# OpenMV-Shield-DESKTOP-QOJ183D.net
KiCad netlist of a schematic drawn in EAGLE
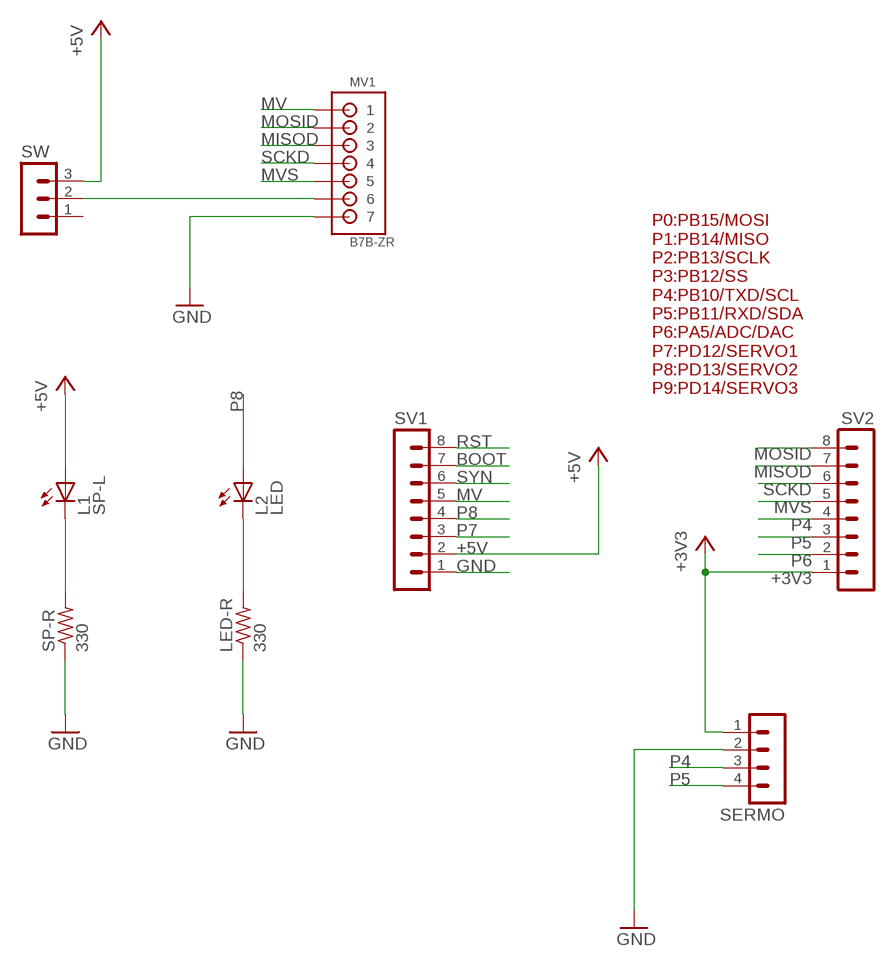
[diagram p0: schematic, sheet 1]

(export (version "E")
  (design (tool "Eeschema 10.0.6"))
  (components
    (comp (ref "L1")
      (value "SP-L")
      (footprint "eagle-import:CHIPLED_0805")
      (libsource (lib "eagle-import") (part "LEDCHIPLED_0805"))
    )
    (comp (ref "L2")
      (value "LED")
      (footprint "eagle-import:CHIPLED_0805")
      (libsource (lib "eagle-import") (part "LEDCHIPLED_0805"))
    )
    (comp (ref "LED-R")
      (value "330")
      (footprint "eagle-import:R0805")
      (libsource (lib "eagle-import") (part "R-US_R0805"))
    )
    (comp (ref "MV1")
      (value "B7B-ZR")
      (footprint "eagle-import:B7B-ZR")
      (libsource (lib "eagle-import") (part "B7B-ZR"))
    )
    (comp (ref "SERMO")
      (value "MA04-1")
      (footprint "eagle-import:MA04-1")
      (libsource (lib "eagle-import") (part "MA04-1"))
    )
    (comp (ref "SP-R")
      (value "330")
      (footprint "eagle-import:R0805")
      (libsource (lib "eagle-import") (part "R-US_R0805"))
    )
    (comp (ref "SV1")
      (value "MA08-1")
      (footprint "eagle-import:MA08-1")
      (libsource (lib "eagle-import") (part "MA08-1"))
    )
    (comp (ref "SV2")
      (value "MA08-1")
      (footprint "eagle-import:MA08-1")
      (libsource (lib "eagle-import") (part "MA08-1"))
    )
    (comp (ref "SW")
      (value "MA03-1")
      (footprint "eagle-import:MA03-1")
      (libsource (lib "eagle-import") (part "MA03-1"))
    )
  )
  (nets
    (net (code "1") (name "+3V3") (class "Default")
      (node (ref "SERMO") (pin "1") (pinfunction "1_1") (pintype "passive"))
      (node (ref "SV2") (pin "1") (pinfunction "1_1") (pintype "passive"))
    )
    (net (code "2") (name "+5V") (class "Default")
      (node (ref "L1") (pin "A") (pinfunction "A_A") (pintype "passive"))
      (node (ref "SV1") (pin "2") (pinfunction "2_2") (pintype "passive"))
      (node (ref "SW") (pin "3") (pinfunction "3_3") (pintype "passive"))
    )
    (net (code "3") (name "/BOOT") (class "Default")
      (node (ref "SV1") (pin "7") (pinfunction "7_7") (pintype "passive"))
    )
    (net (code "4") (name "/MISOD") (class "Default")
      (node (ref "MV1") (pin "3") (pinfunction "3_3") (pintype "bidirectional"))
      (node (ref "SV2") (pin "7") (pinfunction "7_7") (pintype "passive"))
    )
    (net (code "5") (name "/MOSID") (class "Default")
      (node (ref "MV1") (pin "2") (pinfunction "2_2") (pintype "bidirectional"))
      (node (ref "SV2") (pin "8") (pinfunction "8_8") (pintype "passive"))
    )
    (net (code "6") (name "/MV") (class "Default")
      (node (ref "MV1") (pin "1") (pinfunction "1_1") (pintype "bidirectional"))
      (node (ref "SV1") (pin "5") (pinfunction "5_5") (pintype "passive"))
    )
    (net (code "7") (name "/MVS") (class "Default")
      (node (ref "MV1") (pin "5") (pinfunction "5_5") (pintype "bidirectional"))
      (node (ref "SV2") (pin "5") (pinfunction "5_5") (pintype "passive"))
    )
    (net (code "8") (name "/P4") (class "Default")
      (node (ref "SERMO") (pin "3") (pinfunction "3_3") (pintype "passive"))
      (node (ref "SV2") (pin "4") (pinfunction "4_4") (pintype "passive"))
    )
    (net (code "9") (name "/P5") (class "Default")
      (node (ref "SERMO") (pin "4") (pinfunction "4_4") (pintype "passive"))
      (node (ref "SV2") (pin "3") (pinfunction "3_3") (pintype "passive"))
    )
    (net (code "10") (name "/P6") (class "Default")
      (node (ref "SV2") (pin "2") (pinfunction "2_2") (pintype "passive"))
    )
    (net (code "11") (name "/P7") (class "Default")
      (node (ref "SV1") (pin "3") (pinfunction "3_3") (pintype "passive"))
    )
    (net (code "12") (name "/P8") (class "Default")
      (node (ref "L2") (pin "A") (pinfunction "A_A") (pintype "passive"))
      (node (ref "SV1") (pin "4") (pinfunction "4_4") (pintype "passive"))
    )
    (net (code "13") (name "/RST") (class "Default")
      (node (ref "SV1") (pin "8") (pinfunction "8_8") (pintype "passive"))
    )
    (net (code "14") (name "/SCKD") (class "Default")
      (node (ref "MV1") (pin "4") (pinfunction "4_4") (pintype "bidirectional"))
      (node (ref "SV2") (pin "6") (pinfunction "6_6") (pintype "passive"))
    )
    (net (code "15") (name "/SYN") (class "Default")
      (node (ref "SV1") (pin "6") (pinfunction "6_6") (pintype "passive"))
    )
    (net (code "16") (name "GND") (class "Default")
      (node (ref "LED-R") (pin "1") (pinfunction "1_1") (pintype "passive"))
      (node (ref "MV1") (pin "7") (pinfunction "7_7") (pintype "bidirectional"))
      (node (ref "SERMO") (pin "2") (pinfunction "2_2") (pintype "passive"))
      (node (ref "SP-R") (pin "1") (pinfunction "1_1") (pintype "passive"))
      (node (ref "SV1") (pin "1") (pinfunction "1_1") (pintype "passive"))
    )
    (net (code "17") (name "Net-(L1-PadC)") (class "Default")
      (node (ref "L1") (pin "C") (pinfunction "C_C") (pintype "passive"))
      (node (ref "SP-R") (pin "2") (pinfunction "2_2") (pintype "passive"))
    )
    (net (code "18") (name "Net-(L2-PadC)") (class "Default")
      (node (ref "L2") (pin "C") (pinfunction "C_C") (pintype "passive"))
      (node (ref "LED-R") (pin "2") (pinfunction "2_2") (pintype "passive"))
    )
    (net (code "19") (name "Net-(MV1-Pad6)") (class "Default")
      (node (ref "MV1") (pin "6") (pinfunction "6_6") (pintype "bidirectional"))
      (node (ref "SW") (pin "2") (pinfunction "2_2") (pintype "passive"))
    )
    (net (code "20") (name "unconnected-(SW-Pad1)") (class "Default")
      (node (ref "SW") (pin "1") (pinfunction "1_1") (pintype "passive"))
    )
  )
)
